# ESP32_Screen.net
KiCad netlist of a schematic drawn in EasyEDA
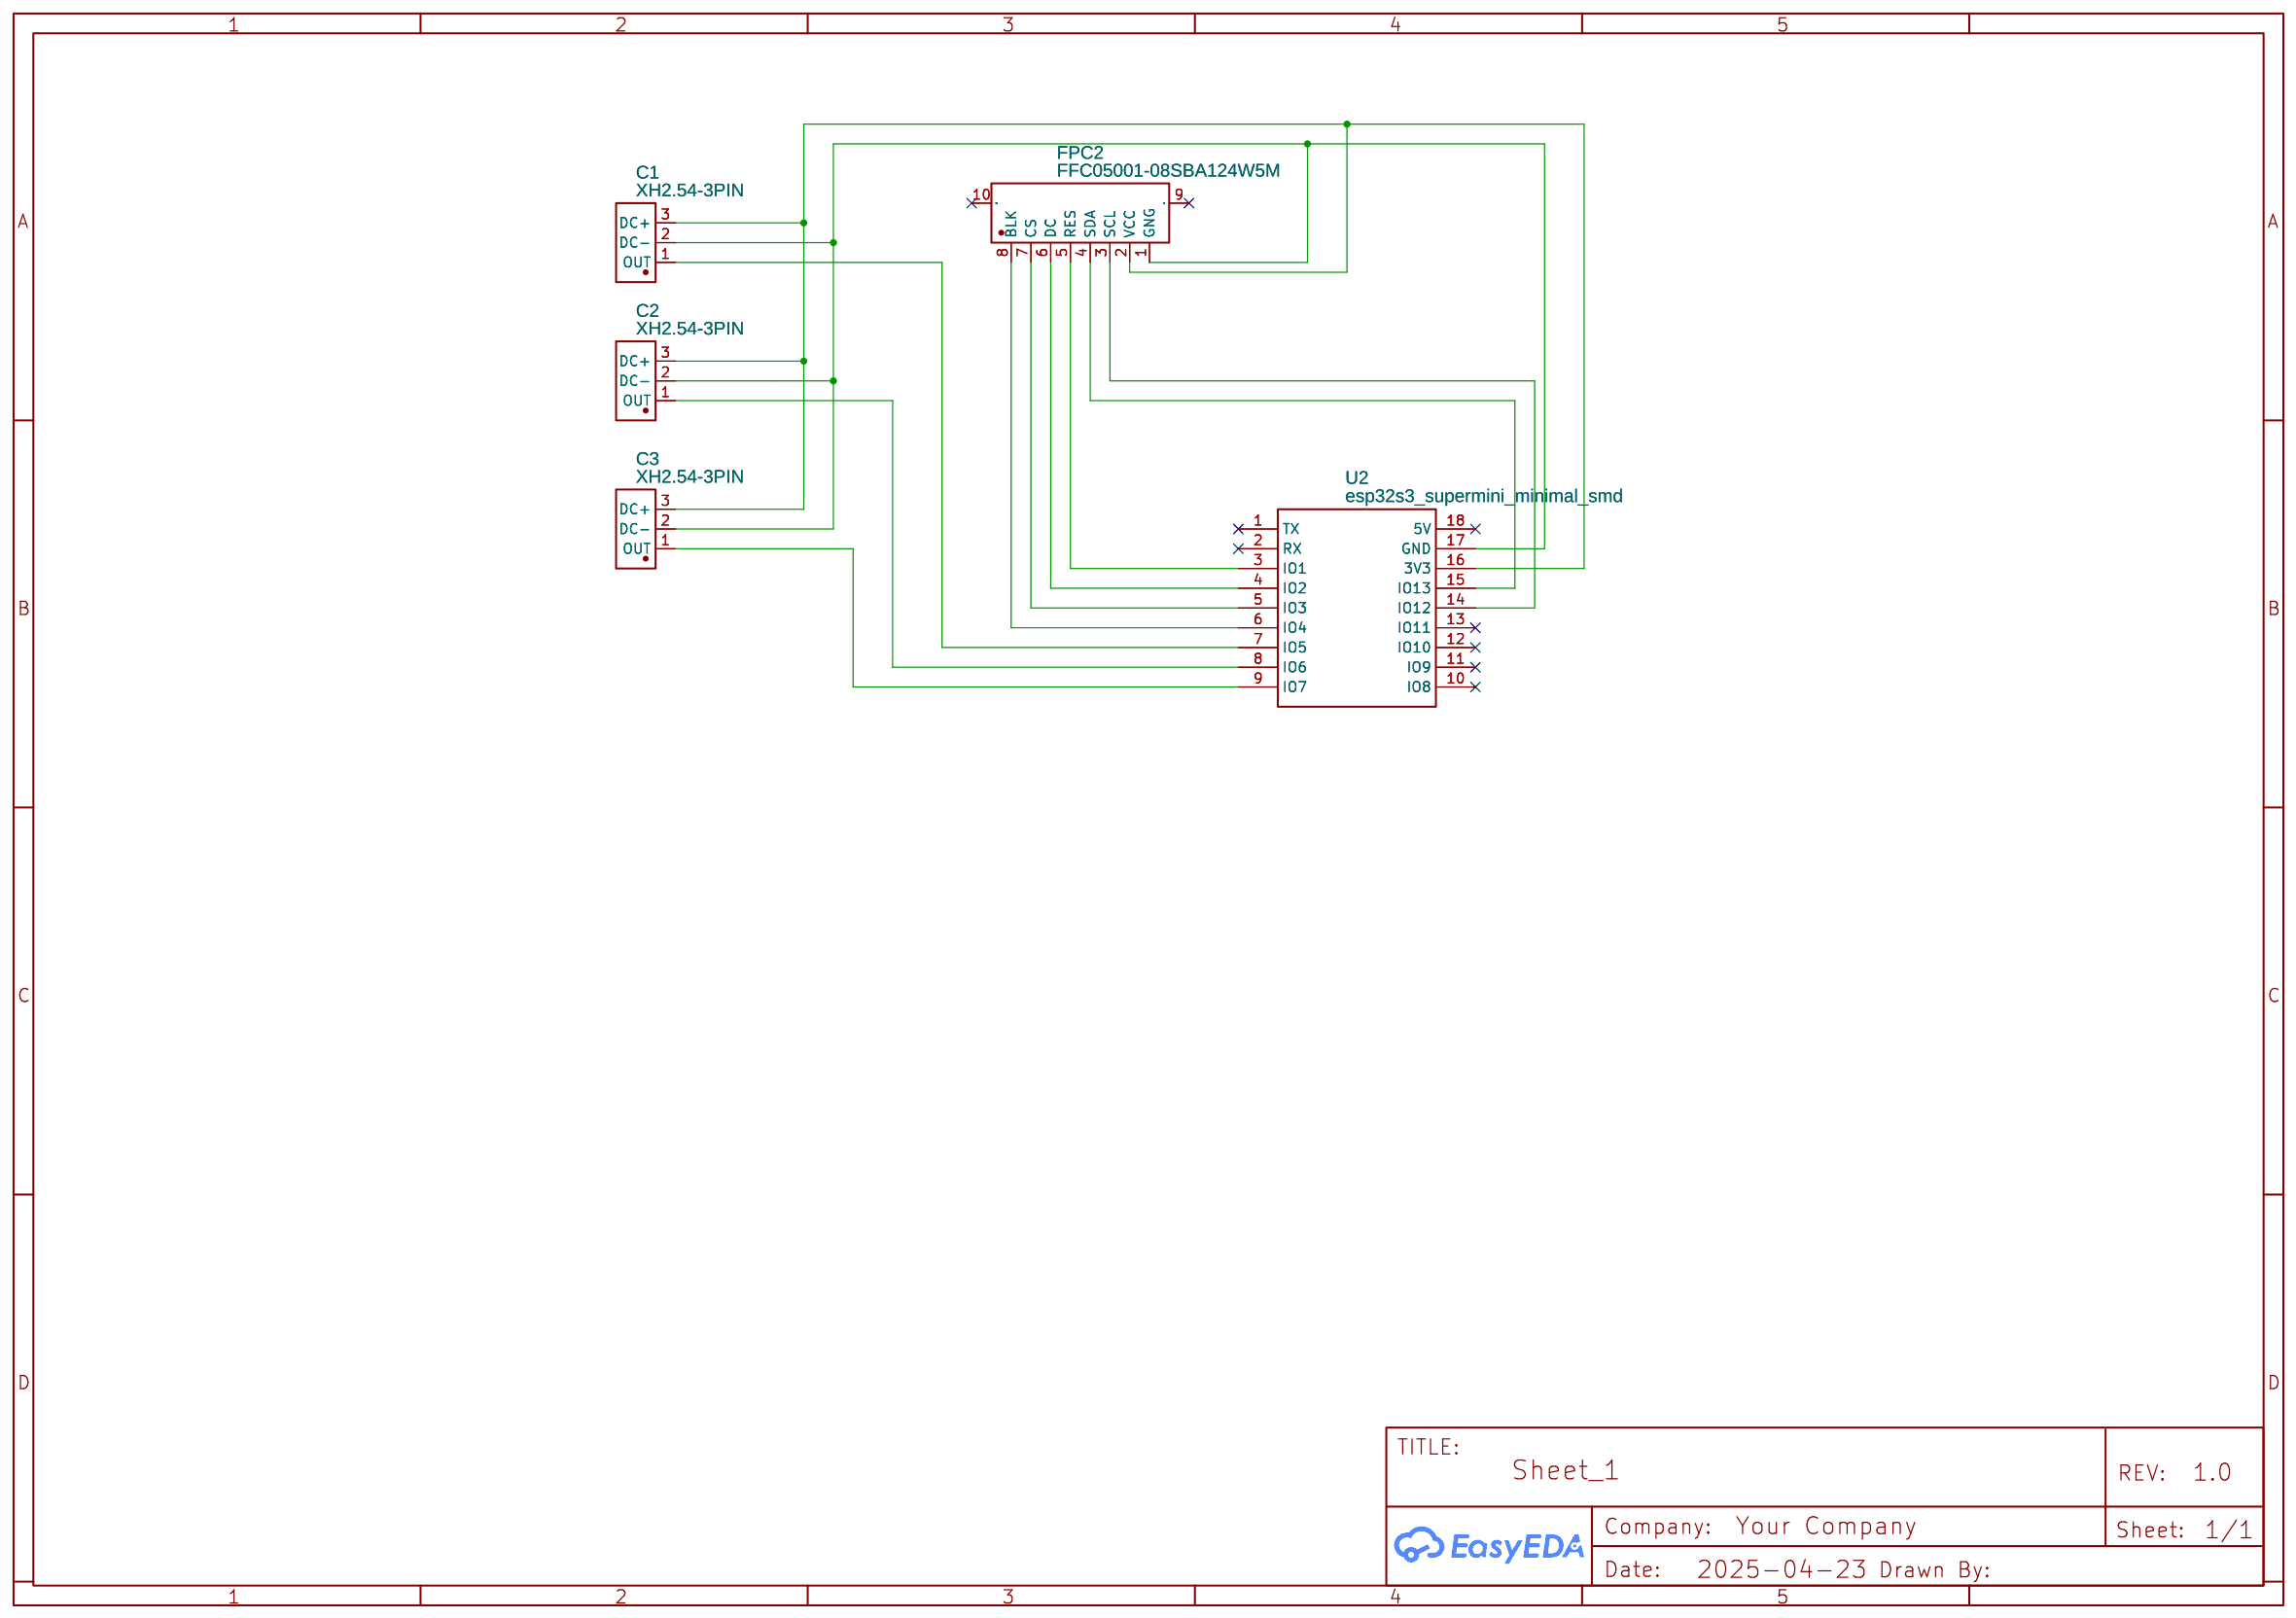
[diagram p0: schematic sheet]

(export (version "E")
  (design (tool "Eeschema 10.0.6"))
  (components
    (comp (ref "C1") (value "XH2.54-3PIN") (libsource (lib "") (part "XH2.54-3PIN")))
    (comp (ref "C2") (value "XH2.54-3PIN") (libsource (lib "") (part "XH2.54-3PIN")))
    (comp (ref "C3") (value "XH2.54-3PIN") (libsource (lib "") (part "XH2.54-3PIN")))
    (comp (ref "FPC2")
      (value "FFC05001-08SBA124W5M")
      (fields (field (name "Manufacturer") "TXGA(特思嘉)"))
      (libsource (lib "") (part "FFC05001-08SBA124W5M"))
    )
    (comp (ref "U2")
      (value "esp32s3_supermini_minimal_smd")
      (libsource (lib "") (part "esp32s3_supermini_minimal_smd"))
    )
  )
  (nets
    (net (code "1") (name "Net-(C1-DC+)") (class "Default")
      (node (ref "C1") (pin "3") (pinfunction "DC+_3") (pintype "unspecified"))
      (node (ref "C2") (pin "3") (pinfunction "DC+_3") (pintype "unspecified"))
      (node (ref "C3") (pin "3") (pinfunction "DC+_3") (pintype "unspecified"))
      (node (ref "FPC2") (pin "2") (pinfunction "VCC_2") (pintype "unspecified"))
      (node (ref "U2") (pin "16") (pinfunction "3V3_16") (pintype "unspecified"))
    )
    (net (code "2") (name "Net-(C1-DC-)") (class "Default")
      (node (ref "C1") (pin "2") (pinfunction "DC-_2") (pintype "unspecified"))
      (node (ref "C2") (pin "2") (pinfunction "DC-_2") (pintype "unspecified"))
      (node (ref "C3") (pin "2") (pinfunction "DC-_2") (pintype "unspecified"))
      (node (ref "FPC2") (pin "1") (pinfunction "GNG_1") (pintype "unspecified"))
      (node (ref "U2") (pin "17") (pinfunction "GND_17") (pintype "unspecified"))
    )
    (net (code "3") (name "Net-(C1-OUT)") (class "Default")
      (node (ref "C1") (pin "1") (pinfunction "OUT_1") (pintype "unspecified"))
      (node (ref "U2") (pin "7") (pinfunction "IO5_7") (pintype "unspecified"))
    )
    (net (code "4") (name "Net-(C2-OUT)") (class "Default")
      (node (ref "C2") (pin "1") (pinfunction "OUT_1") (pintype "unspecified"))
      (node (ref "U2") (pin "8") (pinfunction "IO6_8") (pintype "unspecified"))
    )
    (net (code "5") (name "Net-(C3-OUT)") (class "Default")
      (node (ref "C3") (pin "1") (pinfunction "OUT_1") (pintype "unspecified"))
      (node (ref "U2") (pin "9") (pinfunction "IO7_9") (pintype "unspecified"))
    )
    (net (code "6") (name "Net-(FPC2-BLK)") (class "Default")
      (node (ref "FPC2") (pin "8") (pinfunction "BLK_8") (pintype "unspecified"))
      (node (ref "U2") (pin "6") (pinfunction "IO4_6") (pintype "unspecified"))
    )
    (net (code "7") (name "Net-(FPC2-CS)") (class "Default")
      (node (ref "FPC2") (pin "7") (pinfunction "CS_7") (pintype "unspecified"))
      (node (ref "U2") (pin "5") (pinfunction "IO3_5") (pintype "unspecified"))
    )
    (net (code "8") (name "Net-(FPC2-DC)") (class "Default")
      (node (ref "FPC2") (pin "6") (pinfunction "DC_6") (pintype "unspecified"))
      (node (ref "U2") (pin "4") (pinfunction "IO2_4") (pintype "unspecified"))
    )
    (net (code "9") (name "Net-(FPC2-RES)") (class "Default")
      (node (ref "FPC2") (pin "5") (pinfunction "RES_5") (pintype "unspecified"))
      (node (ref "U2") (pin "3") (pinfunction "IO1_3") (pintype "unspecified"))
    )
    (net (code "10") (name "Net-(FPC2-SCL)") (class "Default")
      (node (ref "FPC2") (pin "3") (pinfunction "SCL_3") (pintype "unspecified"))
      (node (ref "U2") (pin "14") (pinfunction "IO12_14") (pintype "unspecified"))
    )
    (net (code "11") (name "Net-(FPC2-SDA)") (class "Default")
      (node (ref "FPC2") (pin "4") (pinfunction "SDA_4") (pintype "unspecified"))
      (node (ref "U2") (pin "15") (pinfunction "IO13_15") (pintype "unspecified"))
    )
    (net (code "12") (name "unconnected-(FPC2-Pad9)") (class "Default")
      (node (ref "FPC2") (pin "9") (pinfunction "9_9") (pintype "unspecified+no_connect"))
    )
    (net (code "13") (name "unconnected-(FPC2-Pad10)") (class "Default")
      (node (ref "FPC2") (pin "10") (pinfunction "10_10") (pintype "unspecified+no_connect"))
    )
    (net (code "14") (name "unconnected-(U2-5V-Pad18)") (class "Default")
      (node (ref "U2") (pin "18") (pinfunction "5V_18") (pintype "unspecified+no_connect"))
    )
    (net (code "15") (name "unconnected-(U2-IO8-Pad10)") (class "Default")
      (node (ref "U2") (pin "10") (pinfunction "IO8_10") (pintype "unspecified+no_connect"))
    )
    (net (code "16") (name "unconnected-(U2-IO9-Pad11)") (class "Default")
      (node (ref "U2") (pin "11") (pinfunction "IO9_11") (pintype "unspecified+no_connect"))
    )
    (net (code "17") (name "unconnected-(U2-IO10-Pad12)") (class "Default")
      (node (ref "U2") (pin "12") (pinfunction "IO10_12") (pintype "unspecified+no_connect"))
    )
    (net (code "18") (name "unconnected-(U2-IO11-Pad13)") (class "Default")
      (node (ref "U2") (pin "13") (pinfunction "IO11_13") (pintype "unspecified+no_connect"))
    )
    (net (code "19") (name "unconnected-(U2-RX-Pad2)") (class "Default")
      (node (ref "U2") (pin "2") (pinfunction "RX_2") (pintype "unspecified+no_connect"))
    )
    (net (code "20") (name "unconnected-(U2-TX-Pad1)") (class "Default")
      (node (ref "U2") (pin "1") (pinfunction "TX_1") (pintype "unspecified+no_connect"))
    )
  )
)
